# Sheet1.net
KiCad netlist of a schematic drawn in Altium Designer
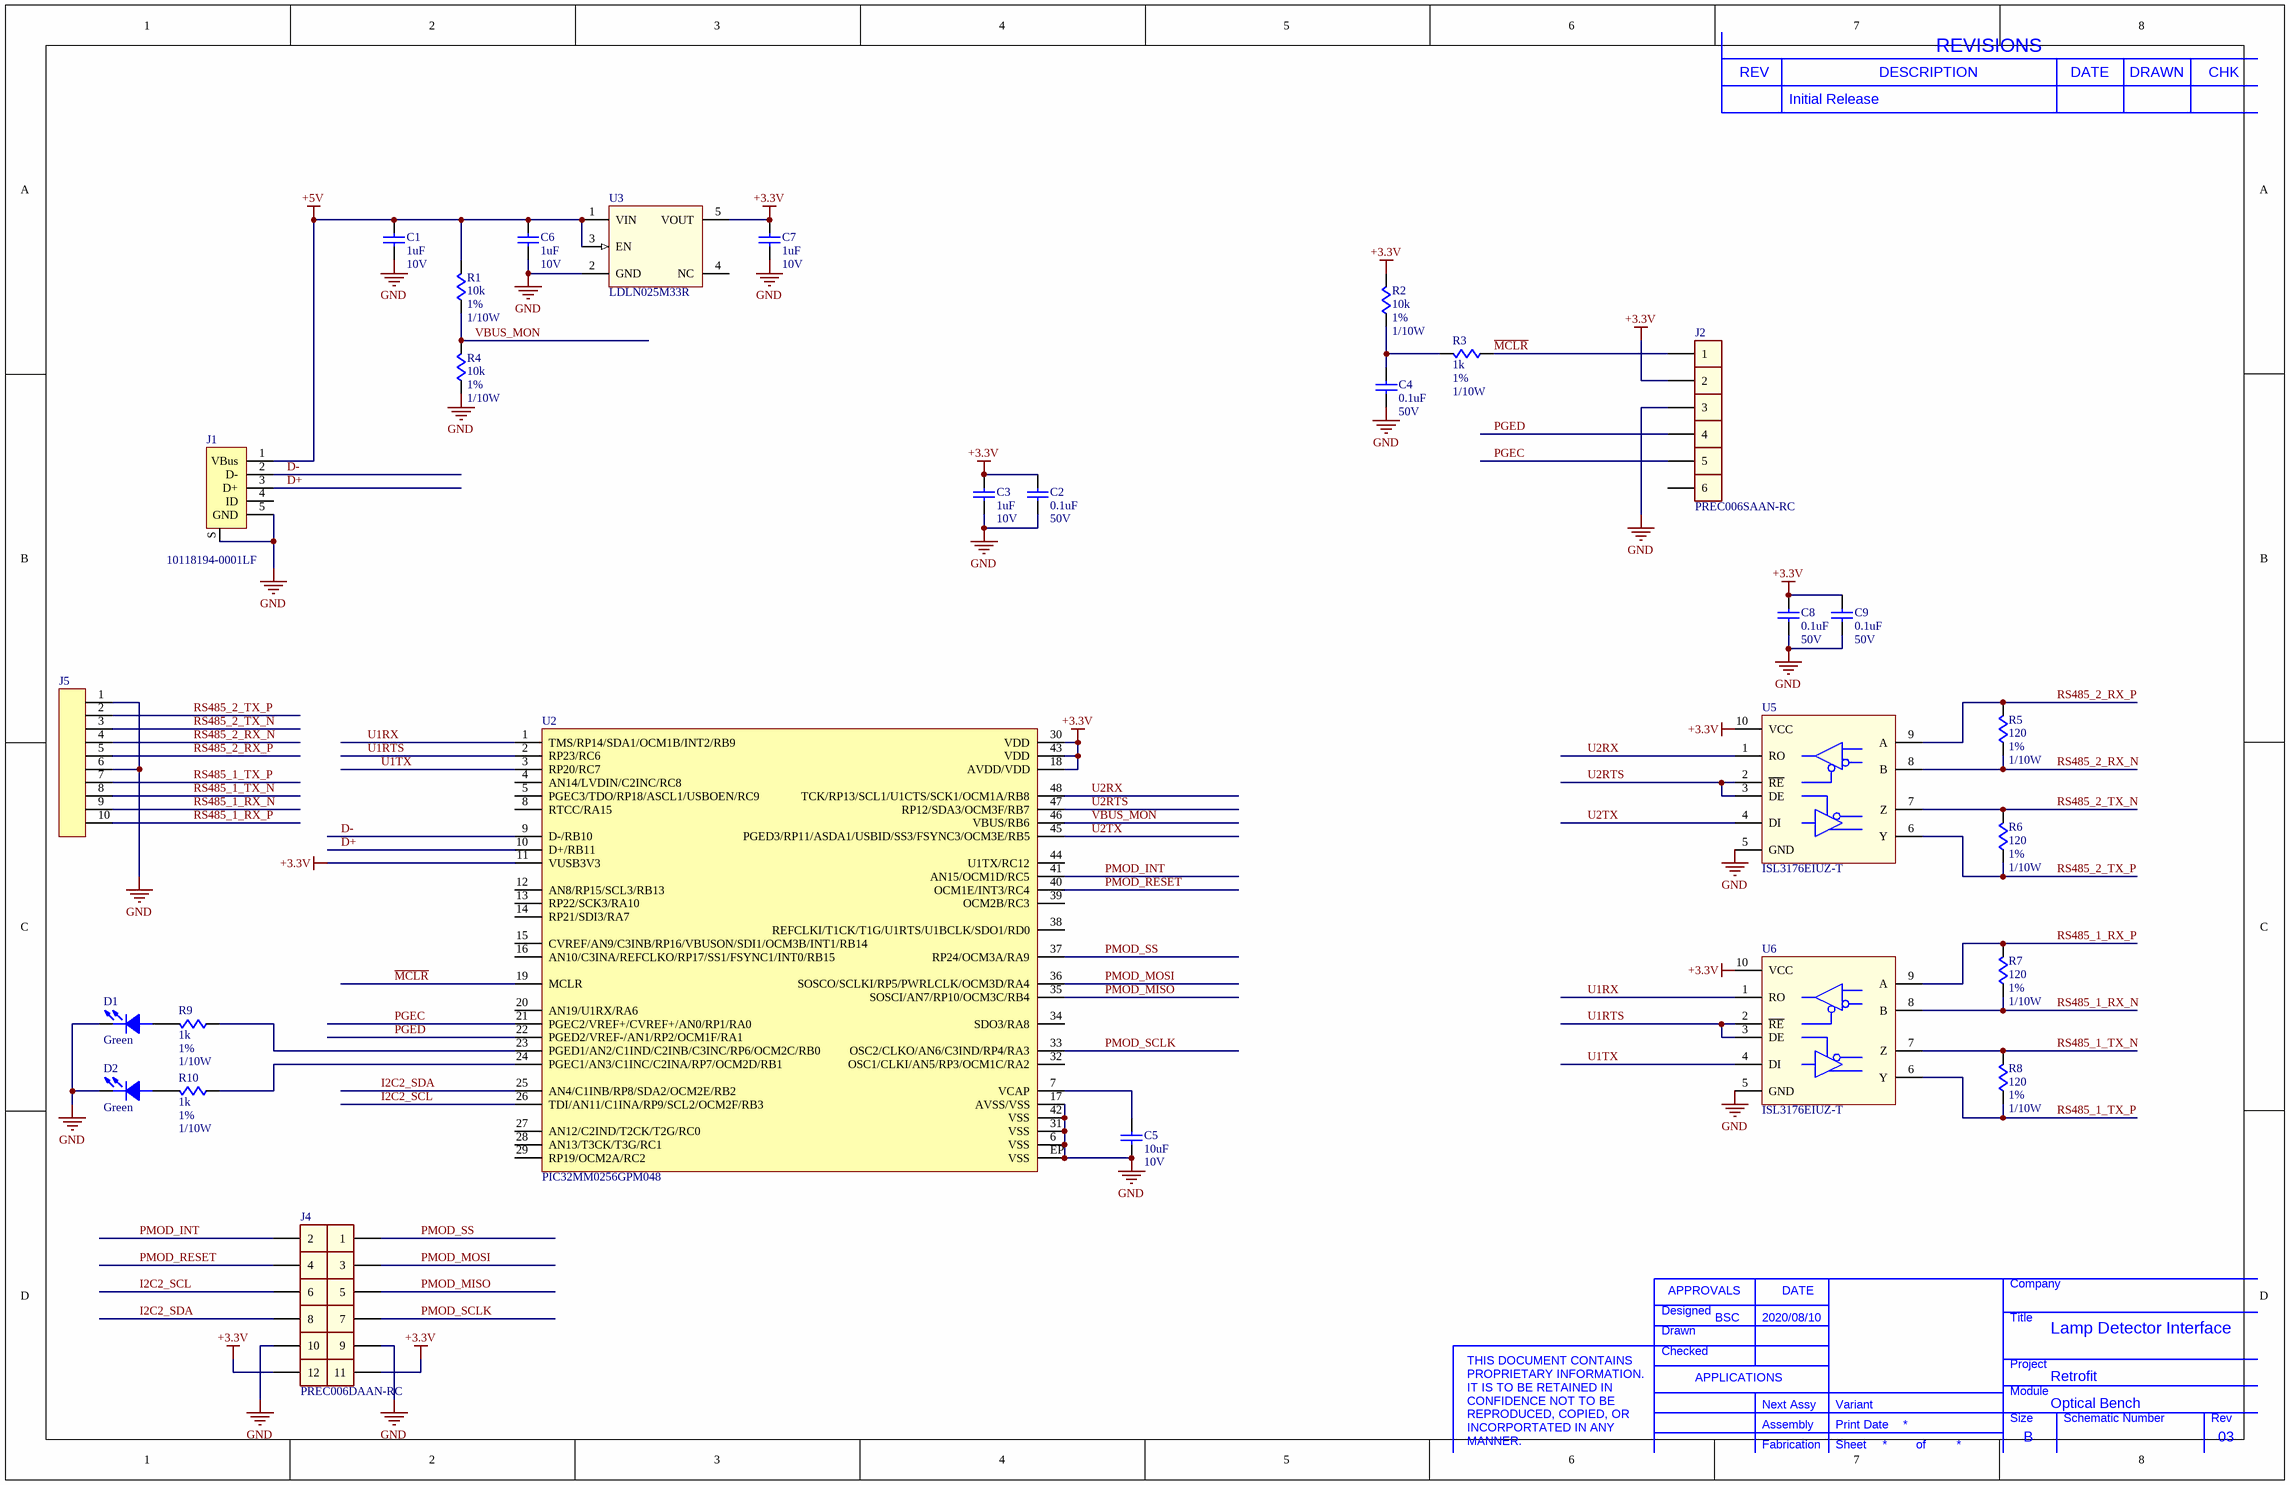
[diagram p0: Sheet1.SchDoc]

(export (version "E")
  (design (tool "Eeschema 10.0.6"))
  (components
    (comp (ref "C1")
      (value "1uF")
      (footprint "CAP_0603")
      (description "Cap Cer 1uF 10V 10% X5R 0603")
      (fields
        (field (name "VOLTAGE") "10V")
        (field (name "PART NUMBER") "2")
        (field (name "TOLERANCE") "10%")
      )
      (libsource (lib "parts_lib") (part "CAP"))
    )
    (comp (ref "C2")
      (value "0.1uF")
      (footprint "CAP_0603")
      (description "Cap Cer 0.1uF 50V 10% X7R 0603")
      (fields
        (field (name "VOLTAGE") "50V")
        (field (name "PART NUMBER") "8")
        (field (name "TOLERANCE") "10%")
      )
      (libsource (lib "parts_lib") (part "CAP"))
    )
    (comp (ref "C3")
      (value "1uF")
      (footprint "CAP_0603")
      (description "Cap Cer 1uF 10V 10% X5R 0603")
      (fields
        (field (name "VOLTAGE") "10V")
        (field (name "PART NUMBER") "2")
        (field (name "TOLERANCE") "10%")
      )
      (libsource (lib "parts_lib") (part "CAP"))
    )
    (comp (ref "C4")
      (value "0.1uF")
      (footprint "CAP_0603")
      (description "Cap Cer 0.1uF 50V 10% X7R 0603")
      (fields
        (field (name "VOLTAGE") "50V")
        (field (name "PART NUMBER") "8")
        (field (name "TOLERANCE") "10%")
      )
      (libsource (lib "parts_lib") (part "CAP"))
    )
    (comp (ref "C5")
      (value "10uF")
      (footprint "CAP_0603")
      (description "Cap Cer 10uF 10V 10% X5R 0603")
      (fields
        (field (name "VOLTAGE") "10V")
        (field (name "PART NUMBER") "11")
        (field (name "TOLERANCE") "10%")
      )
      (libsource (lib "parts_lib") (part "CAP"))
    )
    (comp (ref "C6")
      (value "1uF")
      (footprint "CAP_0603")
      (description "Cap Cer 1uF 10V 10% X5R 0603")
      (fields
        (field (name "VOLTAGE") "10V")
        (field (name "PART NUMBER") "2")
        (field (name "TOLERANCE") "10%")
      )
      (libsource (lib "parts_lib") (part "CAP"))
    )
    (comp (ref "C7")
      (value "1uF")
      (footprint "CAP_0603")
      (description "Cap Cer 1uF 10V 10% X5R 0603")
      (fields
        (field (name "VOLTAGE") "10V")
        (field (name "PART NUMBER") "2")
        (field (name "TOLERANCE") "10%")
      )
      (libsource (lib "parts_lib") (part "CAP"))
    )
    (comp (ref "C8")
      (value "0.1uF")
      (footprint "CAP_0603")
      (description "Cap Cer 0.1uF 50V 10% X7R 0603")
      (fields
        (field (name "VOLTAGE") "50V")
        (field (name "PART NUMBER") "8")
        (field (name "TOLERANCE") "10%")
      )
      (libsource (lib "parts_lib") (part "CAP"))
    )
    (comp (ref "C9")
      (value "0.1uF")
      (footprint "CAP_0603")
      (description "Cap Cer 0.1uF 50V 10% X7R 0603")
      (fields
        (field (name "VOLTAGE") "50V")
        (field (name "PART NUMBER") "8")
        (field (name "TOLERANCE") "10%")
      )
      (libsource (lib "parts_lib") (part "CAP"))
    )
    (comp (ref "D1")
      (value "Green")
      (footprint "DIO_0603")
      (description "Dio LED Green 2V 0603")
      (fields (field (name "PART NUMBER") "13") (field (name "VOLTAGE") "2V"))
      (libsource (lib "parts_lib") (part "LED"))
    )
    (comp (ref "D2")
      (value "Green")
      (footprint "DIO_0603")
      (description "Dio LED Green 2V 0603")
      (fields (field (name "PART NUMBER") "13") (field (name "VOLTAGE") "2V"))
      (libsource (lib "parts_lib") (part "LED"))
    )
    (comp (ref "J1")
      (value "10118194-0001LF")
      (footprint "CONN_USB_MICRO_B_RA")
      (description "Conn Receptacle 10118194-0001LF 0.65mm USB Micro B RA")
      (fields (field (name "PART NUMBER") "67"))
      (libsource (lib "parts_lib") (part "CONN_USB_AB"))
    )
    (comp (ref "J2")
      (value "PREC006SAAN-RC")
      (footprint "CONN_Male_1x6")
      (description "Conn HDR PREC006SAAN-RC 0.1\" 3A Male 1x6")
      (fields (field (name "PART NUMBER") "236"))
      (libsource (lib "parts_lib") (part "CONN_1x6"))
    )
    (comp (ref "J4")
      (value "PREC006DAAN-RC")
      (footprint "CONN_Male_2x6z")
      (description "Conn HDR PREC006DAAN-RC 0.1\" 3A Male 2x6z")
      (fields (field (name "PART NUMBER") "239"))
      (libsource (lib "parts_lib") (part "CONN_2x6z"))
    )
    (comp (ref "J5")
      (value "PREC010SAAN-RC")
      (footprint "CONN_Male_1x10")
      (description "Conn HDR PREC010SAAN-RC 0.1\" 3A Male 1x10")
      (fields (field (name "PART NUMBER") "238"))
      (libsource (lib "parts_lib") (part "CONN_1x10"))
    )
    (comp (ref "R1")
      (value "10k")
      (footprint "RES_0603")
      (description "Res Thick 10k 75V 1/10W 1% 0603")
      (fields
        (field (name "TOLERANCE") "1%")
        (field (name "POWER") "1/10W")
        (field (name "PART NUMBER") "27")
        (field (name "VOLTAGE") "75V")
      )
      (libsource (lib "parts_lib") (part "RES"))
    )
    (comp (ref "R2")
      (value "10k")
      (footprint "RES_0603")
      (description "Res Thick 10k 75V 1/10W 1% 0603")
      (fields
        (field (name "TOLERANCE") "1%")
        (field (name "POWER") "1/10W")
        (field (name "PART NUMBER") "27")
        (field (name "VOLTAGE") "75V")
      )
      (libsource (lib "parts_lib") (part "RES"))
    )
    (comp (ref "R3")
      (value "1k")
      (footprint "RES_0603")
      (description "Res Thick 1k 75V 1/10W 1% 0603")
      (fields
        (field (name "TOLERANCE") "1%")
        (field (name "POWER") "1/10W")
        (field (name "PART NUMBER") "23")
        (field (name "VOLTAGE") "75V")
      )
      (libsource (lib "parts_lib") (part "RES"))
    )
    (comp (ref "R4")
      (value "10k")
      (footprint "RES_0603")
      (description "Res Thick 10k 75V 1/10W 1% 0603")
      (fields
        (field (name "TOLERANCE") "1%")
        (field (name "POWER") "1/10W")
        (field (name "PART NUMBER") "27")
        (field (name "VOLTAGE") "75V")
      )
      (libsource (lib "parts_lib") (part "RES"))
    )
    (comp (ref "R5")
      (value "120")
      (footprint "RES_0603")
      (description "Res Thick 120 75V 1/10W 1% 0603")
      (fields
        (field (name "TOLERANCE") "1%")
        (field (name "POWER") "1/10W")
        (field (name "PART NUMBER") "21")
        (field (name "VOLTAGE") "75V")
      )
      (libsource (lib "parts_lib") (part "RES"))
    )
    (comp (ref "R6")
      (value "120")
      (footprint "RES_0603")
      (description "Res Thick 120 75V 1/10W 1% 0603")
      (fields
        (field (name "TOLERANCE") "1%")
        (field (name "POWER") "1/10W")
        (field (name "PART NUMBER") "21")
        (field (name "VOLTAGE") "75V")
      )
      (libsource (lib "parts_lib") (part "RES"))
    )
    (comp (ref "R7")
      (value "120")
      (footprint "RES_0603")
      (description "Res Thick 120 75V 1/10W 1% 0603")
      (fields
        (field (name "TOLERANCE") "1%")
        (field (name "POWER") "1/10W")
        (field (name "PART NUMBER") "21")
        (field (name "VOLTAGE") "75V")
      )
      (libsource (lib "parts_lib") (part "RES"))
    )
    (comp (ref "R8")
      (value "120")
      (footprint "RES_0603")
      (description "Res Thick 120 75V 1/10W 1% 0603")
      (fields
        (field (name "TOLERANCE") "1%")
        (field (name "POWER") "1/10W")
        (field (name "PART NUMBER") "21")
        (field (name "VOLTAGE") "75V")
      )
      (libsource (lib "parts_lib") (part "RES"))
    )
    (comp (ref "R9")
      (value "1k")
      (footprint "RES_0603")
      (description "Res Thick 1k 75V 1/10W 1% 0603")
      (fields
        (field (name "TOLERANCE") "1%")
        (field (name "POWER") "1/10W")
        (field (name "PART NUMBER") "23")
        (field (name "VOLTAGE") "75V")
      )
      (libsource (lib "parts_lib") (part "RES"))
    )
    (comp (ref "R10")
      (value "1k")
      (footprint "RES_0603")
      (description "Res Thick 1k 75V 1/10W 1% 0603")
      (fields
        (field (name "TOLERANCE") "1%")
        (field (name "POWER") "1/10W")
        (field (name "PART NUMBER") "23")
        (field (name "VOLTAGE") "75V")
      )
      (libsource (lib "parts_lib") (part "RES"))
    )
    (comp (ref "U2")
      (value "PIC32MM0256GPM048")
      (footprint "UQFN-48EP")
      (description "IC MCU PIC32MM0256GPM048 2-3.6V UQFN-48EP")
      (fields (field (name "PART NUMBER") "234") (field (name "VOLTAGE") "2-3.6V"))
      (libsource (lib "parts_lib") (part "MCU_PIC32MMxxxxGPM048"))
    )
    (comp (ref "U3")
      (value "LDLN025M33R")
      (footprint "SOT23-5")
      (description "IC Reg LDO LDLN025M33R 250mA 3.3V OUT SOT23-5")
      (fields (field (name "PART NUMBER") "206"))
      (libsource (lib "parts_lib") (part "VREG_LDO_5P_EN"))
    )
    (comp (ref "U5")
      (value "ISL3176EIUZ-T")
      (footprint "MSOP-10")
      (description "IC Comm ISL3176EIUZ-T 3-3.6V RS422/RS485 FULL DUPLEX MSOP-10")
      (fields (field (name "PART NUMBER") "205") (field (name "VOLTAGE") "3-3.6V"))
      (libsource (lib "parts_lib") (part "IC_RS485_FULL"))
    )
    (comp (ref "U6")
      (value "ISL3176EIUZ-T")
      (footprint "MSOP-10")
      (description "IC Comm ISL3176EIUZ-T 3-3.6V RS422/RS485 FULL DUPLEX MSOP-10")
      (fields (field (name "PART NUMBER") "205") (field (name "VOLTAGE") "3-3.6V"))
      (libsource (lib "parts_lib") (part "IC_RS485_FULL"))
    )
  )
  (nets
    (net (code "1") (name "+3.3V") (class "Default")
      (node (ref "C2") (pin "1") (pinfunction "1_1") (pintype "passive"))
      (node (ref "C3") (pin "1") (pinfunction "1_1") (pintype "passive"))
      (node (ref "C7") (pin "1") (pinfunction "1_1") (pintype "passive"))
      (node (ref "C8") (pin "1") (pinfunction "1_1") (pintype "passive"))
      (node (ref "C9") (pin "1") (pinfunction "1_1") (pintype "passive"))
      (node (ref "J2") (pin "2") (pinfunction "2_2") (pintype "passive"))
      (node (ref "J4") (pin "11") (pinfunction "11_11") (pintype "passive"))
      (node (ref "J4") (pin "12") (pinfunction "12_12") (pintype "passive"))
      (node (ref "R2") (pin "2") (pinfunction "2_2") (pintype "passive"))
      (node (ref "U2") (pin "11") (pinfunction "VUSB3V3_11") (pintype "passive"))
      (node (ref "U2") (pin "18") (pinfunction "AVDD/VDD_18") (pintype "power_in"))
      (node (ref "U2") (pin "30") (pinfunction "VDD_30") (pintype "power_in"))
      (node (ref "U2") (pin "43") (pinfunction "VDD_43") (pintype "power_in"))
      (node (ref "U3") (pin "5") (pinfunction "VOUT_5") (pintype "power_in"))
      (node (ref "U5") (pin "10") (pinfunction "VCC_10") (pintype "passive"))
      (node (ref "U6") (pin "10") (pinfunction "VCC_10") (pintype "passive"))
    )
    (net (code "2") (name "+5V") (class "Default")
      (node (ref "C1") (pin "1") (pinfunction "1_1") (pintype "passive"))
      (node (ref "C6") (pin "1") (pinfunction "1_1") (pintype "passive"))
      (node (ref "J1") (pin "1") (pinfunction "VBus_1") (pintype "passive"))
      (node (ref "R1") (pin "2") (pinfunction "2_2") (pintype "passive"))
      (node (ref "U3") (pin "1") (pinfunction "VIN_1") (pintype "power_in"))
      (node (ref "U3") (pin "3") (pinfunction "EN_3") (pintype "input"))
    )
    (net (code "3") (name "/D+") (class "Default")
      (node (ref "J1") (pin "3") (pinfunction "D+_3") (pintype "passive"))
      (node (ref "U2") (pin "10") (pinfunction "D+/RB11_10") (pintype "passive"))
    )
    (net (code "4") (name "/D-") (class "Default")
      (node (ref "J1") (pin "2") (pinfunction "D-_2") (pintype "passive"))
      (node (ref "U2") (pin "9") (pinfunction "D-/RB10_9") (pintype "passive"))
    )
    (net (code "5") (name "/I2C2_SCL") (class "Default")
      (node (ref "J4") (pin "6") (pinfunction "6_6") (pintype "passive"))
      (node (ref "U2") (pin "26") (pinfunction "TDI/AN11/C1INA/RP9/SCL2/OCM2F/RB3_26") (pintype "passive"))
    )
    (net (code "6") (name "/I2C2_SDA") (class "Default")
      (node (ref "J4") (pin "8") (pinfunction "8_8") (pintype "passive"))
      (node (ref "U2") (pin "25") (pinfunction "AN4/C1INB/RP8/SDA2/OCM2E/RB2_25") (pintype "passive"))
    )
    (net (code "7") (name "/PGEC") (class "Default")
      (node (ref "J2") (pin "5") (pinfunction "5_5") (pintype "passive"))
      (node (ref "U2") (pin "21") (pinfunction "PGEC2/VREF+/CVREF+/AN0/RP1/RA0_21") (pintype "passive"))
    )
    (net (code "8") (name "/PGED") (class "Default")
      (node (ref "J2") (pin "4") (pinfunction "4_4") (pintype "passive"))
      (node (ref "U2") (pin "22") (pinfunction "PGED2/VREF-/AN1/RP2/OCM1F/RA1_22") (pintype "passive"))
    )
    (net (code "9") (name "/PMOD_INT") (class "Default")
      (node (ref "J4") (pin "2") (pinfunction "2_2") (pintype "passive"))
      (node (ref "U2") (pin "41") (pinfunction "AN15/OCM1D/RC5_41") (pintype "passive"))
    )
    (net (code "10") (name "/PMOD_MISO") (class "Default")
      (node (ref "J4") (pin "5") (pinfunction "5_5") (pintype "passive"))
      (node (ref "U2") (pin "35") (pinfunction "SOSCI/AN7/RP10/OCM3C/RB4_35") (pintype "passive"))
    )
    (net (code "11") (name "/PMOD_MOSI") (class "Default")
      (node (ref "J4") (pin "3") (pinfunction "3_3") (pintype "passive"))
      (node (ref "U2") (pin "36") (pinfunction "SOSCO/SCLKI/RP5/PWRLCLK/OCM3D/RA4_36") (pintype "passive"))
    )
    (net (code "12") (name "/PMOD_RESET") (class "Default")
      (node (ref "J4") (pin "4") (pinfunction "4_4") (pintype "passive"))
      (node (ref "U2") (pin "40") (pinfunction "OCM1E/INT3/RC4_40") (pintype "passive"))
    )
    (net (code "13") (name "/PMOD_SCLK") (class "Default")
      (node (ref "J4") (pin "7") (pinfunction "7_7") (pintype "passive"))
      (node (ref "U2") (pin "33") (pinfunction "OSC2/CLKO/AN6/C3IND/RP4/RA3_33") (pintype "passive"))
    )
    (net (code "14") (name "/PMOD_SS") (class "Default")
      (node (ref "J4") (pin "1") (pinfunction "1_1") (pintype "passive"))
      (node (ref "U2") (pin "37") (pinfunction "RP24/OCM3A/RA9_37") (pintype "passive"))
    )
    (net (code "15") (name "/RS485_1_RX_N") (class "Default")
      (node (ref "J5") (pin "9") (pinfunction "9_9") (pintype "passive"))
      (node (ref "R7") (pin "1") (pinfunction "1_1") (pintype "passive"))
      (node (ref "U6") (pin "8") (pinfunction "B_8") (pintype "passive"))
    )
    (net (code "16") (name "/RS485_1_RX_P") (class "Default")
      (node (ref "J5") (pin "10") (pinfunction "10_10") (pintype "passive"))
      (node (ref "R7") (pin "2") (pinfunction "2_2") (pintype "passive"))
      (node (ref "U6") (pin "9") (pinfunction "A_9") (pintype "passive"))
    )
    (net (code "17") (name "/RS485_1_TX_N") (class "Default")
      (node (ref "J5") (pin "8") (pinfunction "8_8") (pintype "passive"))
      (node (ref "R8") (pin "2") (pinfunction "2_2") (pintype "passive"))
      (node (ref "U6") (pin "7") (pinfunction "Z_7") (pintype "passive"))
    )
    (net (code "18") (name "/RS485_1_TX_P") (class "Default")
      (node (ref "J5") (pin "7") (pinfunction "7_7") (pintype "passive"))
      (node (ref "R8") (pin "1") (pinfunction "1_1") (pintype "passive"))
      (node (ref "U6") (pin "6") (pinfunction "Y_6") (pintype "passive"))
    )
    (net (code "19") (name "/RS485_2_RX_N") (class "Default")
      (node (ref "J5") (pin "4") (pinfunction "4_4") (pintype "passive"))
      (node (ref "R5") (pin "1") (pinfunction "1_1") (pintype "passive"))
      (node (ref "U5") (pin "8") (pinfunction "B_8") (pintype "passive"))
    )
    (net (code "20") (name "/RS485_2_RX_P") (class "Default")
      (node (ref "J5") (pin "5") (pinfunction "5_5") (pintype "passive"))
      (node (ref "R5") (pin "2") (pinfunction "2_2") (pintype "passive"))
      (node (ref "U5") (pin "9") (pinfunction "A_9") (pintype "passive"))
    )
    (net (code "21") (name "/RS485_2_TX_N") (class "Default")
      (node (ref "J5") (pin "3") (pinfunction "3_3") (pintype "passive"))
      (node (ref "R6") (pin "2") (pinfunction "2_2") (pintype "passive"))
      (node (ref "U5") (pin "7") (pinfunction "Z_7") (pintype "passive"))
    )
    (net (code "22") (name "/RS485_2_TX_P") (class "Default")
      (node (ref "J5") (pin "2") (pinfunction "2_2") (pintype "passive"))
      (node (ref "R6") (pin "1") (pinfunction "1_1") (pintype "passive"))
      (node (ref "U5") (pin "6") (pinfunction "Y_6") (pintype "passive"))
    )
    (net (code "23") (name "/U1RTS") (class "Default")
      (node (ref "U2") (pin "2") (pinfunction "RP23/RC6_2") (pintype "passive"))
      (node (ref "U6") (pin "2") (pinfunction "~{RE}_2") (pintype "passive"))
      (node (ref "U6") (pin "3") (pinfunction "DE_3") (pintype "passive"))
    )
    (net (code "24") (name "/U1RX") (class "Default")
      (node (ref "U2") (pin "1") (pinfunction "TMS/RP14/SDA1/OCM1B/INT2/RB9_1") (pintype "passive"))
      (node (ref "U6") (pin "1") (pinfunction "RO_1") (pintype "passive"))
    )
    (net (code "25") (name "/U1TX") (class "Default")
      (node (ref "U2") (pin "3") (pinfunction "RP20/RC7_3") (pintype "passive"))
      (node (ref "U6") (pin "4") (pinfunction "DI_4") (pintype "passive"))
    )
    (net (code "26") (name "/U2RTS") (class "Default")
      (node (ref "U2") (pin "47") (pinfunction "RP12/SDA3/OCM3F/RB7_47") (pintype "passive"))
      (node (ref "U5") (pin "2") (pinfunction "~{RE}_2") (pintype "passive"))
      (node (ref "U5") (pin "3") (pinfunction "DE_3") (pintype "passive"))
    )
    (net (code "27") (name "/U2RX") (class "Default")
      (node (ref "U2") (pin "48") (pinfunction "TCK/RP13/SCL1/U1CTS/SCK1/OCM1A/RB8_48") (pintype "passive"))
      (node (ref "U5") (pin "1") (pinfunction "RO_1") (pintype "passive"))
    )
    (net (code "28") (name "/U2TX") (class "Default")
      (node (ref "U2") (pin "45") (pinfunction "PGED3/RP11/ASDA1/USBID/SS3/FSYNC3/OCM3E/RB5_45") (pintype "passive"))
      (node (ref "U5") (pin "4") (pinfunction "DI_4") (pintype "passive"))
    )
    (net (code "29") (name "/VBUS_MON") (class "Default")
      (node (ref "R1") (pin "1") (pinfunction "1_1") (pintype "passive"))
      (node (ref "R4") (pin "2") (pinfunction "2_2") (pintype "passive"))
      (node (ref "U2") (pin "46") (pinfunction "VBUS/RB6_46") (pintype "passive"))
    )
    (net (code "30") (name "/~{MCLR}") (class "Default")
      (node (ref "J2") (pin "1") (pinfunction "1_1") (pintype "passive"))
      (node (ref "R3") (pin "1") (pinfunction "1_1") (pintype "passive"))
      (node (ref "U2") (pin "19") (pinfunction "MCLR_19") (pintype "passive"))
    )
    (net (code "31") (name "GND") (class "Default")
      (node (ref "C1") (pin "2") (pinfunction "2_2") (pintype "passive"))
      (node (ref "C2") (pin "2") (pinfunction "2_2") (pintype "passive"))
      (node (ref "C3") (pin "2") (pinfunction "2_2") (pintype "passive"))
      (node (ref "C4") (pin "2") (pinfunction "2_2") (pintype "passive"))
      (node (ref "C5") (pin "2") (pinfunction "2_2") (pintype "passive"))
      (node (ref "C6") (pin "2") (pinfunction "2_2") (pintype "passive"))
      (node (ref "C7") (pin "2") (pinfunction "2_2") (pintype "passive"))
      (node (ref "C8") (pin "2") (pinfunction "2_2") (pintype "passive"))
      (node (ref "C9") (pin "2") (pinfunction "2_2") (pintype "passive"))
      (node (ref "D1") (pin "K") (pinfunction "K_K") (pintype "passive"))
      (node (ref "D2") (pin "K") (pinfunction "K_K") (pintype "passive"))
      (node (ref "J1") (pin "5") (pinfunction "GND_5") (pintype "passive"))
      (node (ref "J1") (pin "S") (pinfunction "S_S") (pintype "passive"))
      (node (ref "J2") (pin "3") (pinfunction "3_3") (pintype "passive"))
      (node (ref "J4") (pin "10") (pinfunction "10_10") (pintype "passive"))
      (node (ref "J4") (pin "9") (pinfunction "9_9") (pintype "passive"))
      (node (ref "J5") (pin "1") (pinfunction "1_1") (pintype "passive"))
      (node (ref "J5") (pin "6") (pinfunction "6_6") (pintype "passive"))
      (node (ref "R4") (pin "1") (pinfunction "1_1") (pintype "passive"))
      (node (ref "U2") (pin "17") (pinfunction "AVSS/VSS_17") (pintype "power_in"))
      (node (ref "U2") (pin "31") (pinfunction "VSS_31") (pintype "power_in"))
      (node (ref "U2") (pin "42") (pinfunction "VSS_42") (pintype "power_in"))
      (node (ref "U2") (pin "6") (pinfunction "VSS_6") (pintype "power_in"))
      (node (ref "U2") (pin "EP") (pinfunction "VSS_EP") (pintype "power_in"))
      (node (ref "U3") (pin "2") (pinfunction "GND_2") (pintype "power_in"))
      (node (ref "U5") (pin "5") (pinfunction "GND_5") (pintype "passive"))
      (node (ref "U6") (pin "5") (pinfunction "GND_5") (pintype "passive"))
    )
    (net (code "32") (name "Net-(C4-Pad1)") (class "Default")
      (node (ref "C4") (pin "1") (pinfunction "1_1") (pintype "passive"))
      (node (ref "R2") (pin "1") (pinfunction "1_1") (pintype "passive"))
      (node (ref "R3") (pin "2") (pinfunction "2_2") (pintype "passive"))
    )
    (net (code "33") (name "Net-(D1-PadA)") (class "Default")
      (node (ref "D1") (pin "A") (pinfunction "A_A") (pintype "passive"))
      (node (ref "R9") (pin "2") (pinfunction "2_2") (pintype "passive"))
    )
    (net (code "34") (name "Net-(D2-PadA)") (class "Default")
      (node (ref "D2") (pin "A") (pinfunction "A_A") (pintype "passive"))
      (node (ref "R10") (pin "2") (pinfunction "2_2") (pintype "passive"))
    )
    (net (code "35") (name "Net-(U2-PGEC1{slash}AN3{slash}C1INC{slash}C2INA{slash}RP7{slash}OCM2D{slash}RB1)") (class "Default")
      (node (ref "R10") (pin "1") (pinfunction "1_1") (pintype "passive"))
      (node (ref "U2") (pin "24") (pinfunction "PGEC1/AN3/C1INC/C2INA/RP7/OCM2D/RB1_24") (pintype "passive"))
    )
    (net (code "36") (name "Net-(U2-PGED1{slash}AN2{slash}C1IND{slash}C2INB{slash}C3INC{slash}RP6{slash}OCM2C{slash}RB0)") (class "Default")
      (node (ref "R9") (pin "1") (pinfunction "1_1") (pintype "passive"))
      (node (ref "U2") (pin "23") (pinfunction "PGED1/AN2/C1IND/C2INB/C3INC/RP6/OCM2C/RB0_23") (pintype "passive"))
    )
    (net (code "37") (name "Net-(U2-VCAP)") (class "Default")
      (node (ref "C5") (pin "1") (pinfunction "1_1") (pintype "passive"))
      (node (ref "U2") (pin "7") (pinfunction "VCAP_7") (pintype "passive"))
    )
    (net (code "38") (name "unconnected-(J1-ID-Pad4)") (class "Default")
      (node (ref "J1") (pin "4") (pinfunction "ID_4") (pintype "passive"))
    )
    (net (code "39") (name "unconnected-(J2-Pad6)") (class "Default")
      (node (ref "J2") (pin "6") (pinfunction "6_6") (pintype "passive"))
    )
    (net (code "40") (name "unconnected-(U2-AN8{slash}RP15{slash}SCL3{slash}RB13-Pad12)") (class "Default")
      (node (ref "U2") (pin "12") (pinfunction "AN8/RP15/SCL3/RB13_12") (pintype "passive"))
    )
    (net (code "41") (name "unconnected-(U2-AN10{slash}C3INA{slash}REFCLKO{slash}RP17{slash}SS1{slash}FSYNC1{slash}INT0{slash}RB15-Pad16)") (class "Default")
      (node (ref "U2") (pin "16") (pinfunction "AN10/C3INA/REFCLKO/RP17/SS1/FSYNC1/INT0/RB15_16") (pintype "passive"))
    )
    (net (code "42") (name "unconnected-(U2-AN12{slash}C2IND{slash}T2CK{slash}T2G{slash}RC0-Pad27)") (class "Default")
      (node (ref "U2") (pin "27") (pinfunction "AN12/C2IND/T2CK/T2G/RC0_27") (pintype "passive"))
    )
    (net (code "43") (name "unconnected-(U2-AN13{slash}T3CK{slash}T3G{slash}RC1-Pad28)") (class "Default")
      (node (ref "U2") (pin "28") (pinfunction "AN13/T3CK/T3G/RC1_28") (pintype "passive"))
    )
    (net (code "44") (name "unconnected-(U2-AN14{slash}LVDIN{slash}C2INC{slash}RC8-Pad4)") (class "Default")
      (node (ref "U2") (pin "4") (pinfunction "AN14/LVDIN/C2INC/RC8_4") (pintype "passive"))
    )
    (net (code "45") (name "unconnected-(U2-AN19{slash}U1RX{slash}RA6-Pad20)") (class "Default")
      (node (ref "U2") (pin "20") (pinfunction "AN19/U1RX/RA6_20") (pintype "passive"))
    )
    (net (code "46") (name "unconnected-(U2-CVREF{slash}AN9{slash}C3INB{slash}RP16{slash}VBUSON{slash}SDI1{slash}OCM3B{slash}INT1{slash}RB14-Pad15)") (class "Default")
      (node (ref "U2") (pin "15") (pinfunction "CVREF/AN9/C3INB/RP16/VBUSON/SDI1/OCM3B/INT1/RB14_15") (pintype "passive"))
    )
    (net (code "47") (name "unconnected-(U2-OCM2B{slash}RC3-Pad39)") (class "Default")
      (node (ref "U2") (pin "39") (pinfunction "OCM2B/RC3_39") (pintype "passive"))
    )
    (net (code "48") (name "unconnected-(U2-OSC1{slash}CLKI{slash}AN5{slash}RP3{slash}OCM1C{slash}RA2-Pad32)") (class "Default")
      (node (ref "U2") (pin "32") (pinfunction "OSC1/CLKI/AN5/RP3/OCM1C/RA2_32") (pintype "passive"))
    )
    (net (code "49") (name "unconnected-(U2-PGEC3{slash}TDO{slash}RP18{slash}ASCL1{slash}USBOEN{slash}RC9-Pad5)") (class "Default")
      (node (ref "U2") (pin "5") (pinfunction "PGEC3/TDO/RP18/ASCL1/USBOEN/RC9_5") (pintype "passive"))
    )
    (net (code "50") (name "unconnected-(U2-REFCLKI{slash}T1CK{slash}T1G{slash}U1RTS{slash}U1BCLK{slash}SDO1{slash}RD0-Pad38)") (class "Default")
      (node (ref "U2") (pin "38") (pinfunction "REFCLKI/T1CK/T1G/U1RTS/U1BCLK/SDO1/RD0_38") (pintype "passive"))
    )
    (net (code "51") (name "unconnected-(U2-RP19{slash}OCM2A{slash}RC2-Pad29)") (class "Default")
      (node (ref "U2") (pin "29") (pinfunction "RP19/OCM2A/RC2_29") (pintype "passive"))
    )
    (net (code "52") (name "unconnected-(U2-RP21{slash}SDI3{slash}RA7-Pad14)") (class "Default")
      (node (ref "U2") (pin "14") (pinfunction "RP21/SDI3/RA7_14") (pintype "passive"))
    )
    (net (code "53") (name "unconnected-(U2-RP22{slash}SCK3{slash}RA10-Pad13)") (class "Default")
      (node (ref "U2") (pin "13") (pinfunction "RP22/SCK3/RA10_13") (pintype "passive"))
    )
    (net (code "54") (name "unconnected-(U2-RTCC{slash}RA15-Pad8)") (class "Default")
      (node (ref "U2") (pin "8") (pinfunction "RTCC/RA15_8") (pintype "passive"))
    )
    (net (code "55") (name "unconnected-(U2-SDO3{slash}RA8-Pad34)") (class "Default")
      (node (ref "U2") (pin "34") (pinfunction "SDO3/RA8_34") (pintype "passive"))
    )
    (net (code "56") (name "unconnected-(U2-U1TX{slash}RC12-Pad44)") (class "Default")
      (node (ref "U2") (pin "44") (pinfunction "U1TX/RC12_44") (pintype "passive"))
    )
    (net (code "57") (name "unconnected-(U3-NC-Pad4)") (class "Default")
      (node (ref "U3") (pin "4") (pinfunction "NC_4") (pintype "passive"))
    )
  )
)
